# pam2803-boost-driver-13mm-mk-2_0.net
KiCad netlist of a schematic drawn in EAGLE
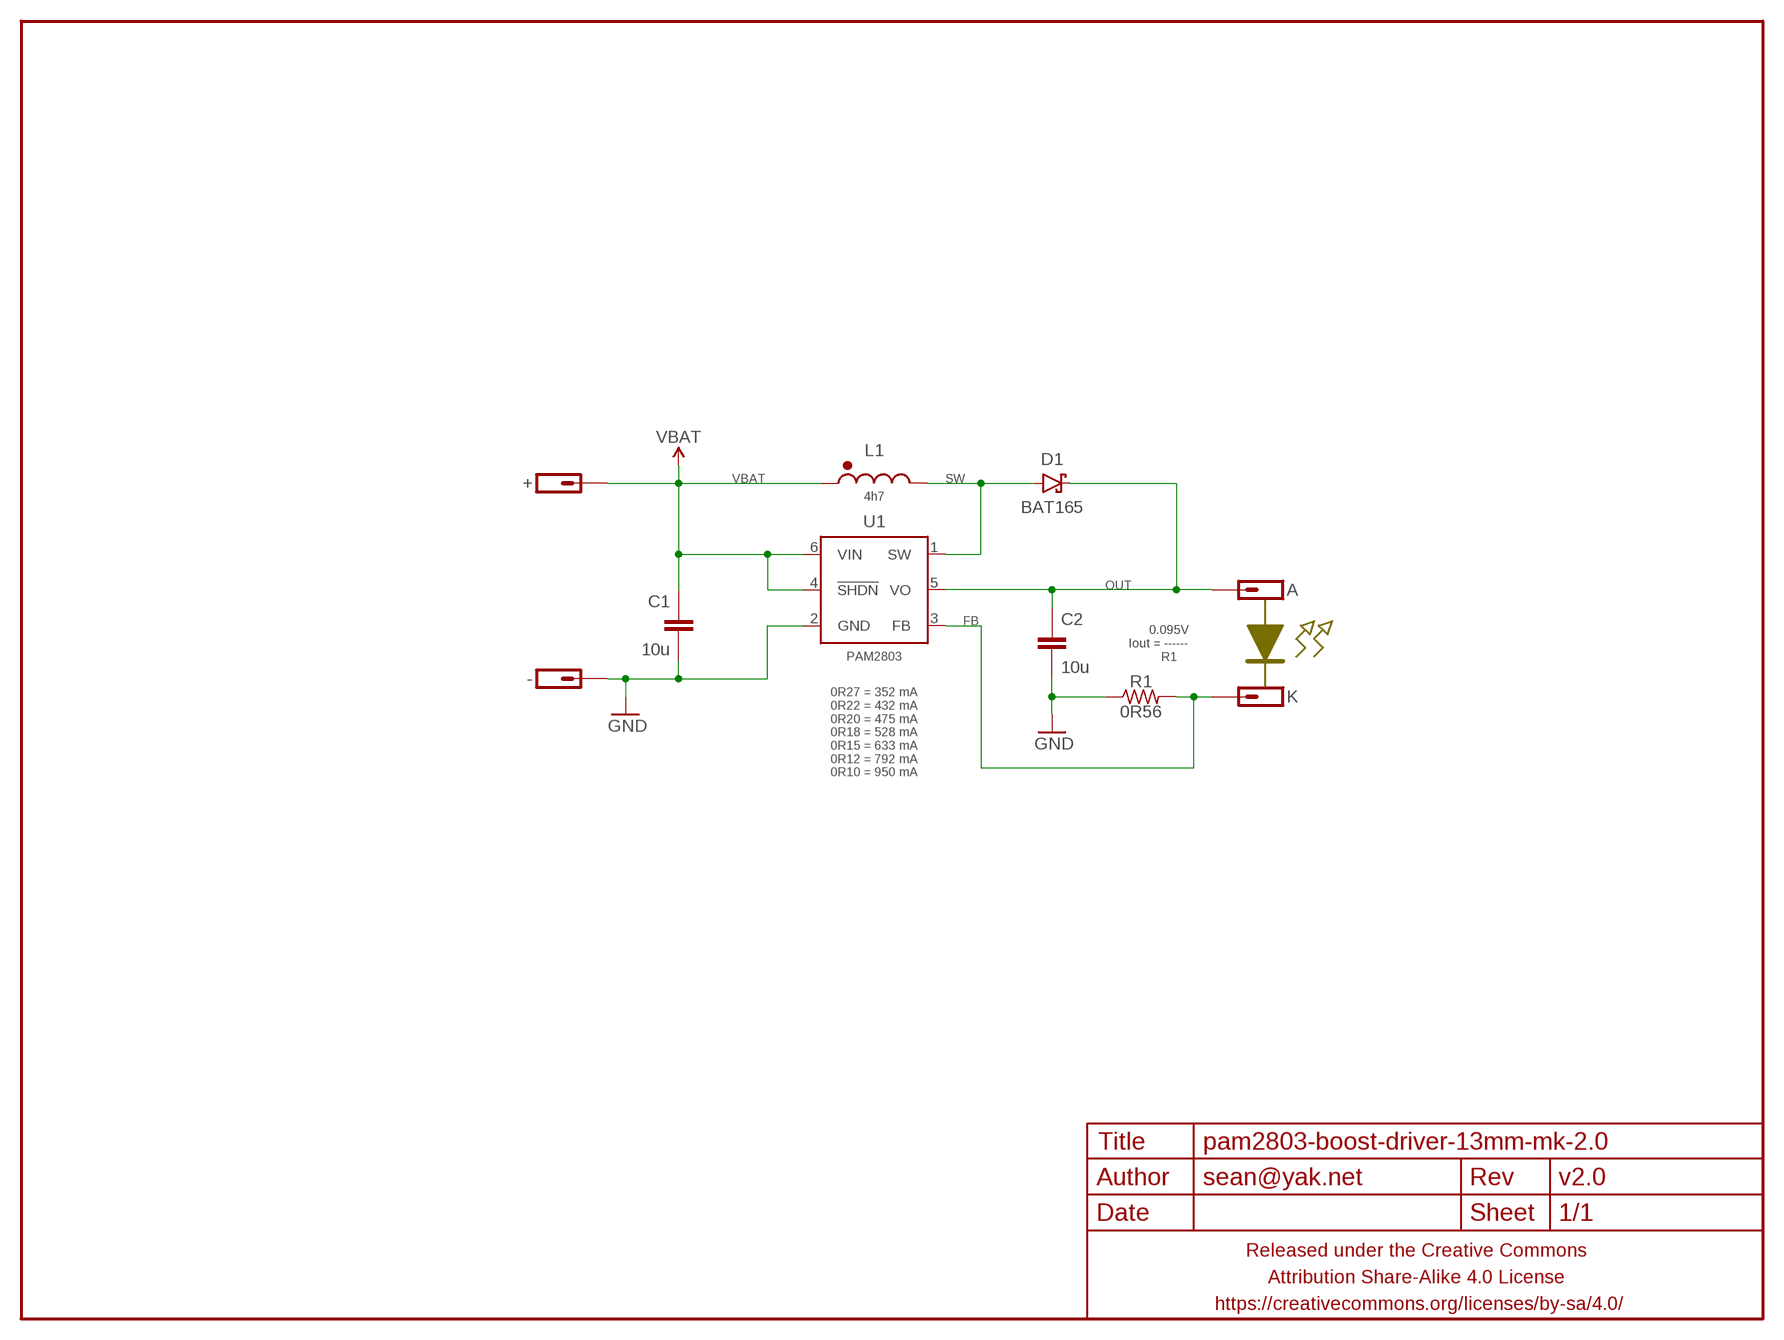
[diagram p0: schematic, sheet 1]

(export (version "E")
  (design (tool "Eeschema 10.0.6"))
  (components
    (comp (ref "+")
      (value "M01NOT-A-VIA-NOPE")
      (footprint "eagle-import:1X01_NOSILK_NOSTOP")
      (libsource (lib "eagle-import") (part "M01NOT-A-VIA-NOPE"))
    )
    (comp (ref "-")
      (value "M01NOT-A-VIA-NOPE")
      (footprint "eagle-import:1X01_NOSILK_NOSTOP")
      (libsource (lib "eagle-import") (part "M01NOT-A-VIA-NOPE"))
    )
    (comp (ref "A")
      (value "M01SMD-1.5MM-DIA-NS")
      (footprint "eagle-import:1X01-SMD-1.5MM-DIA-NS")
      (libsource (lib "eagle-import") (part "M01SMD-1.5MM-DIA-NS"))
    )
    (comp (ref "C1")
      (value "10u")
      (footprint "eagle-import:C0603-TIGHTER")
      (libsource (lib "eagle-import") (part "CAPACITOR-CERAMICC0603-TIGHTER"))
    )
    (comp (ref "C2")
      (value "10u")
      (footprint "eagle-import:C0603-TIGHTER")
      (libsource (lib "eagle-import") (part "CAPACITOR-CERAMICC0603-TIGHTER"))
    )
    (comp (ref "D1")
      (value "BAT165")
      (footprint "eagle-import:SOD323-SCHOTTKY")
      (libsource (lib "eagle-import") (part "DIODE-SCHOTTKYSOD323"))
    )
    (comp (ref "FRAME1")
      (value "FRAME-LETTERNO_PACKAGE")
      (footprint "eagle-import:DUMMY")
      (fields (field (name "DESIGNER") "sean@yak.net") (field (name "VERSION") "v2.0"))
      (libsource (lib "eagle-import") (part "FRAME-LETTERNO_PACKAGE"))
    )
    (comp (ref "K")
      (value "M01SMD-1.5MM-DIA-NS")
      (footprint "eagle-import:1X01-SMD-1.5MM-DIA-NS")
      (libsource (lib "eagle-import") (part "M01SMD-1.5MM-DIA-NS"))
    )
    (comp (ref "L1")
      (value "4h7")
      (footprint "eagle-import:EPL2014")
      (libsource (lib "eagle-import") (part "INDUCTOREPL2014"))
    )
    (comp (ref "R1")
      (value "0R56")
      (footprint "eagle-import:R0603-TIGHTER")
      (libsource (lib "eagle-import") (part "RESISTORR0603-TIGHTER"))
    )
    (comp (ref "U1")
      (value "PAM2803")
      (footprint "eagle-import:SOT23-6")
      (libsource (lib "eagle-import") (part "PAM2803SOT23-6"))
    )
  )
  (nets
    (net (code "1") (name "/FB") (class "Default")
      (node (ref "K") (pin "P$1") (pinfunction "1_P$1") (pintype "passive"))
      (node (ref "R1") (pin "2") (pinfunction "2_2") (pintype "passive"))
      (node (ref "U1") (pin "3") (pinfunction "FB_3") (pintype "bidirectional"))
    )
    (net (code "2") (name "/OUT") (class "Default")
      (node (ref "A") (pin "P$1") (pinfunction "1_P$1") (pintype "passive"))
      (node (ref "C2") (pin "1") (pinfunction "1_1") (pintype "passive"))
      (node (ref "D1") (pin "C") (pinfunction "C_C") (pintype "passive"))
      (node (ref "U1") (pin "5") (pinfunction "VO_5") (pintype "bidirectional"))
    )
    (net (code "3") (name "/SW") (class "Default")
      (node (ref "D1") (pin "A") (pinfunction "A_A") (pintype "passive"))
      (node (ref "L1") (pin "P$2") (pinfunction "2_P$2") (pintype "passive"))
      (node (ref "U1") (pin "1") (pinfunction "SW_1") (pintype "bidirectional"))
    )
    (net (code "4") (name "GND") (class "Default")
      (node (ref "-") (pin "P$1") (pinfunction "1_P$1") (pintype "passive"))
      (node (ref "C1") (pin "2") (pinfunction "2_2") (pintype "passive"))
      (node (ref "C2") (pin "2") (pinfunction "2_2") (pintype "passive"))
      (node (ref "R1") (pin "1") (pinfunction "1_1") (pintype "passive"))
      (node (ref "U1") (pin "2") (pinfunction "GND_2") (pintype "bidirectional"))
    )
    (net (code "5") (name "VBAT") (class "Default")
      (node (ref "+") (pin "P$1") (pinfunction "1_P$1") (pintype "passive"))
      (node (ref "C1") (pin "1") (pinfunction "1_1") (pintype "passive"))
      (node (ref "L1") (pin "P$1") (pinfunction "1_P$1") (pintype "passive"))
      (node (ref "U1") (pin "4") (pinfunction "~{SHDN}_4") (pintype "bidirectional"))
      (node (ref "U1") (pin "6") (pinfunction "VIN_6") (pintype "bidirectional"))
    )
  )
)
